# power-section.net
KiCad netlist of a schematic drawn in Altium Designer
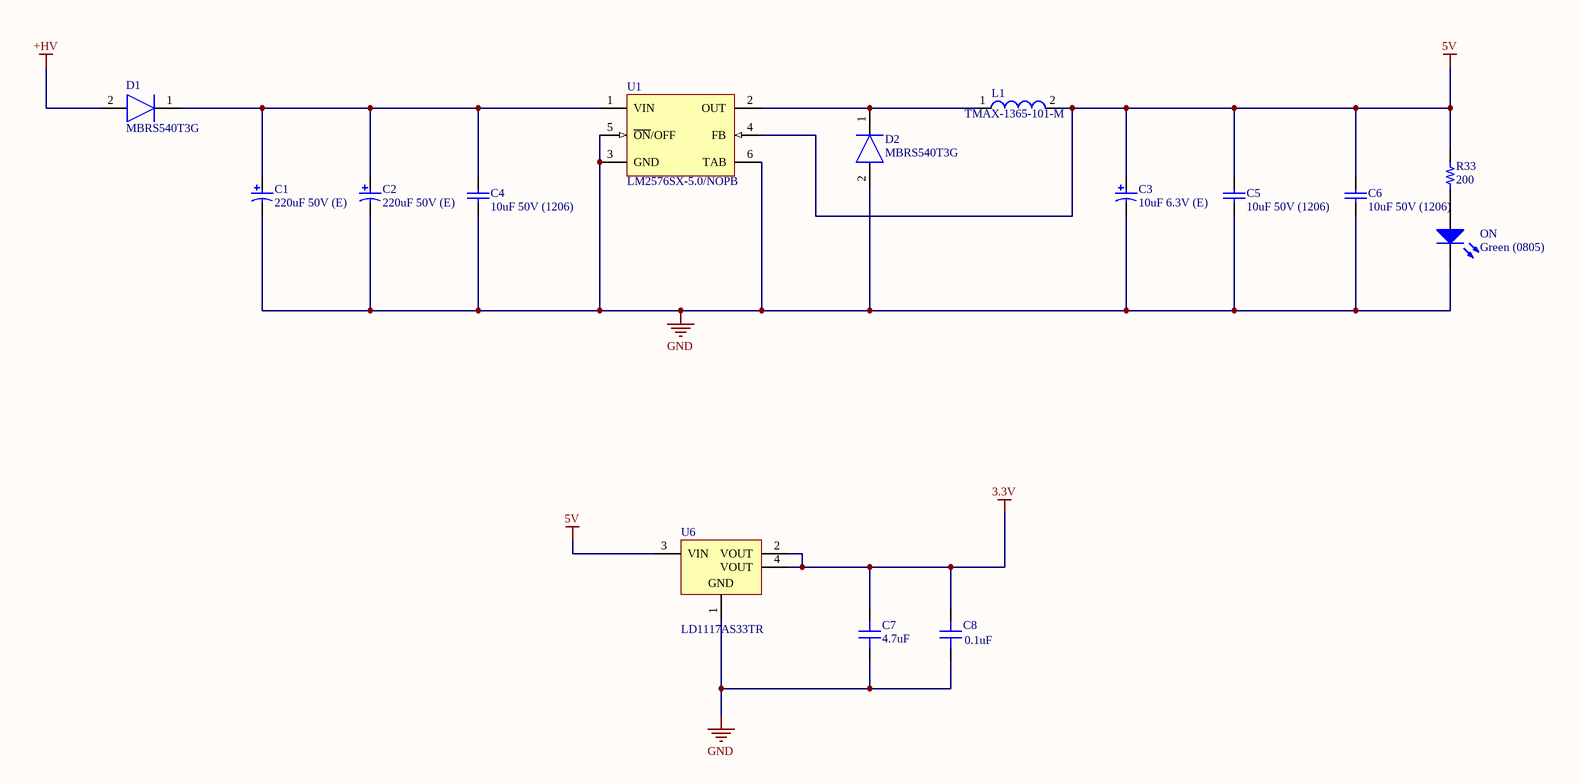
[diagram p0: power-section.SchDoc]

(export (version "E")
  (design (tool "Eeschema 10.0.6"))
  (components
    (comp (ref "C1")
      (value "220uF 50V (E)")
      (footprint "PNSC-EEE-1HA221P_L")
      (fields (field (name "MANUFACTURER") "Panasonic"))
      (libsource (lib "Altium Content Vault") (part "CAP-P-2"))
    )
    (comp (ref "C2")
      (value "220uF 50V (E)")
      (footprint "PNSC-EEE-1HA221P_L")
      (fields (field (name "MANUFACTURER") "Panasonic"))
      (libsource (lib "Altium Content Vault") (part "CAP-P-2"))
    )
    (comp (ref "C3")
      (value "10uF 6.3V (E)")
      (footprint "NIC-CAPA2-8X10_V")
      (fields (field (name "MANUFACTURER") "Nichicon") (field (name "PARTNUMBER") "UUD0J102MNL1GS"))
      (libsource (lib "Altium Content Vault") (part "NIC-CAP-P-2"))
    )
    (comp (ref "C4")
      (value "10uF 50V (1206)")
      (footprint "CAPC3216X229X50LL20T25")
      (description "Chip Capacitor, 10 uF, +/- 10%, 25 V, -55 to 85 degC, 1206 (3216 Metric), RoHS, Tape and Reel")
      (fields (field (name "MANUFACTURER") "AVX"))
      (libsource (lib "Altium Content Vault") (part "CAP-NP-2"))
    )
    (comp (ref "C5")
      (value "10uF 50V (1206)")
      (footprint "CAPC3216X229X50LL20T25")
      (description "Chip Capacitor, 10 uF, +/- 10%, 25 V, -55 to 85 degC, 1206 (3216 Metric), RoHS, Tape and Reel")
      (fields (field (name "MANUFACTURER") "AVX"))
      (libsource (lib "Altium Content Vault") (part "CAP-NP-2"))
    )
    (comp (ref "C6")
      (value "10uF 50V (1206)")
      (footprint "CAPC3216X229X50LL20T25")
      (description "Chip Capacitor, 10 uF, +/- 10%, 25 V, -55 to 85 degC, 1206 (3216 Metric), RoHS, Tape and Reel")
      (fields (field (name "MANUFACTURER") "AVX"))
      (libsource (lib "Altium Content Vault") (part "CAP-NP-2"))
    )
    (comp (ref "C7")
      (value "4.7uF")
      (footprint "CAP 1206_3216 - 1.8MM")
      (description "CAP CERAMIC 16V X5R 1206")
      (fields (field (name "PART NUMBER") "C1206C335K4PACTU") (field (name "MANUFACTURER") "KEMET"))
      (libsource (lib "Celestial Altium Library - altium_library") (part "Capacitor"))
    )
    (comp (ref "C8")
      (value "0.1uF")
      (footprint "CAP 0603_1608")
      (description "CAP CERAMIC 50V X7R 0603")
      (fields
        (field (name "PART NUMBER") "VJ0603Y332JXACW1BC")
        (field (name "MANUFACTURER") "Vishay Vitramon")
      )
      (libsource (lib "Celestial Altium Library - altium_library") (part "Capacitor"))
    )
    (comp (ref "D1")
      (value "MBRS540T3G")
      (footprint "SamacSys:DIOM7958X256N")
      (description "Diode")
      (fields (field (name "MOUSER PART NUMBER") "863-MBRS540T3G") (field (name "RS PART NUMBER") "6880512"))
      (libsource (lib "*") (part "MBRS540T3G"))
    )
    (comp (ref "D2")
      (value "MBRS540T3G")
      (footprint "SamacSys:DIOM7958X256N")
      (description "Diode")
      (fields (field (name "MOUSER PART NUMBER") "863-MBRS540T3G") (field (name "RS PART NUMBER") "6880512"))
      (libsource (lib "*") (part "MBRS540T3G"))
    )
    (comp (ref "L1")
      (value "TMAX-1365-101-M")
      (footprint "WE-HCI-1365")
      (description "SMD Flat Wire High Current Inductor WE-HCI, L=33.0 µH")
      (fields (field (name "MANUFACTURER") "Wuerth Elektronik") (field (name "PARTNUMBER") "7443551331"))
      (libsource (lib "Altium Content Vault") (part "PAS-IND-INDUCTOR-2"))
    )
    (comp (ref "ON")
      (value "Green (0805)")
      (footprint "0805_A")
      (description "SMD mono-color Chip LED, WL-SMCW, Green")
      (fields (field (name "PARTNUMBER") "150080GS75000") (field (name "MANUFACTURER") "Wuerth Elektronik"))
      (libsource (lib "Altium Content Vault") (part "WE-LED_K1A2-2"))
    )
    (comp (ref "R33")
      (value "200")
      (footprint "RES 0603_1608")
      (description "Resistor")
      (fields (field (name "PART NUMBER") "CRCW060329K4FKEA") (field (name "MANUFACTURER") "Vishay Dale"))
      (libsource (lib "Celestial Altium Library - altium_library") (part "Resistor"))
    )
    (comp (ref "U1")
      (value "LM2576SX-5.0/NOPB")
      (footprint "KTT0005B_M")
      (description "SIMPLE SWITCHER® 3A Step-Down Voltage Regulator, 5-pin TO-263, Pb-Free")
      (fields (field (name "MANUFACTURER") "Texas Instruments"))
      (libsource (lib "Altium Content Vault") (part "PM-REG-LM2575HVS-12"))
    )
    (comp (ref "U6")
      (value "LD1117AS33TR")
      (footprint "SOT-223_M")
      (description "1A, Low Drop Positive Voltage Regulator, 3.3V, 4-Pin SOT-223, Tape and Reel")
      (libsource (lib "Altium Content Vault") (part "PM-REG-LD1117-SOT4"))
    )
  )
  (nets
    (net (code "1") (name "+HV") (class "Default")
      (node (ref "D1") (pin "2") (pinfunction "A_2") (pintype "passive"))
    )
    (net (code "2") (name "3.3V") (class "Default")
      (node (ref "C7") (pin "2") (pinfunction "2_2") (pintype "passive"))
      (node (ref "C8") (pin "2") (pinfunction "2_2") (pintype "passive"))
      (node (ref "U6") (pin "2") (pinfunction "VOUT_2") (pintype "power_in"))
      (node (ref "U6") (pin "4") (pinfunction "VOUT_4") (pintype "power_in"))
    )
    (net (code "3") (name "5V") (class "Default")
      (node (ref "C3") (pin "1") (pinfunction "1_1") (pintype "passive"))
      (node (ref "C5") (pin "2") (pinfunction "2_2") (pintype "passive"))
      (node (ref "C6") (pin "2") (pinfunction "2_2") (pintype "passive"))
      (node (ref "L1") (pin "2") (pinfunction "2_2") (pintype "passive"))
      (node (ref "R33") (pin "2") (pinfunction "2_2") (pintype "passive"))
      (node (ref "U1") (pin "4") (pinfunction "FB_4") (pintype "input"))
      (node (ref "U6") (pin "3") (pinfunction "VIN_3") (pintype "power_in"))
    )
    (net (code "4") (name "GND") (class "Default")
      (node (ref "C1") (pin "2") (pinfunction "2_2") (pintype "passive"))
      (node (ref "C2") (pin "2") (pinfunction "2_2") (pintype "passive"))
      (node (ref "C3") (pin "2") (pinfunction "2_2") (pintype "passive"))
      (node (ref "C4") (pin "1") (pinfunction "1_1") (pintype "passive"))
      (node (ref "C5") (pin "1") (pinfunction "1_1") (pintype "passive"))
      (node (ref "C6") (pin "1") (pinfunction "1_1") (pintype "passive"))
      (node (ref "C7") (pin "1") (pinfunction "1_1") (pintype "passive"))
      (node (ref "C8") (pin "1") (pinfunction "1_1") (pintype "passive"))
      (node (ref "D2") (pin "2") (pinfunction "A_2") (pintype "passive"))
      (node (ref "ON") (pin "1") (pinfunction "K_1") (pintype "passive"))
      (node (ref "U1") (pin "3") (pinfunction "GND_3") (pintype "power_in"))
      (node (ref "U1") (pin "5") (pinfunction "~{ON}/OFF_5") (pintype "input"))
      (node (ref "U1") (pin "6") (pinfunction "TAB_6") (pintype "power_in"))
      (node (ref "U6") (pin "1") (pinfunction "GND_1") (pintype "power_in"))
    )
    (net (code "5") (name "Net-(D1-K)") (class "Default")
      (node (ref "C1") (pin "1") (pinfunction "1_1") (pintype "passive"))
      (node (ref "C2") (pin "1") (pinfunction "1_1") (pintype "passive"))
      (node (ref "C4") (pin "2") (pinfunction "2_2") (pintype "passive"))
      (node (ref "D1") (pin "1") (pinfunction "K_1") (pintype "passive"))
      (node (ref "U1") (pin "1") (pinfunction "VIN_1") (pintype "power_in"))
    )
    (net (code "6") (name "Net-(D2-K)") (class "Default")
      (node (ref "D2") (pin "1") (pinfunction "K_1") (pintype "passive"))
      (node (ref "L1") (pin "1") (pinfunction "1_1") (pintype "passive"))
      (node (ref "U1") (pin "2") (pinfunction "OUT_2") (pintype "power_in"))
    )
    (net (code "7") (name "Net-(ON-A)") (class "Default")
      (node (ref "ON") (pin "2") (pinfunction "A_2") (pintype "passive"))
      (node (ref "R33") (pin "1") (pinfunction "1_1") (pintype "passive"))
    )
  )
)
